# SEWERYN_G_ADYSZ_F1_DASHBOARD_SCHEMA_v3.net
KiCad netlist of a schematic drawn in EAGLE
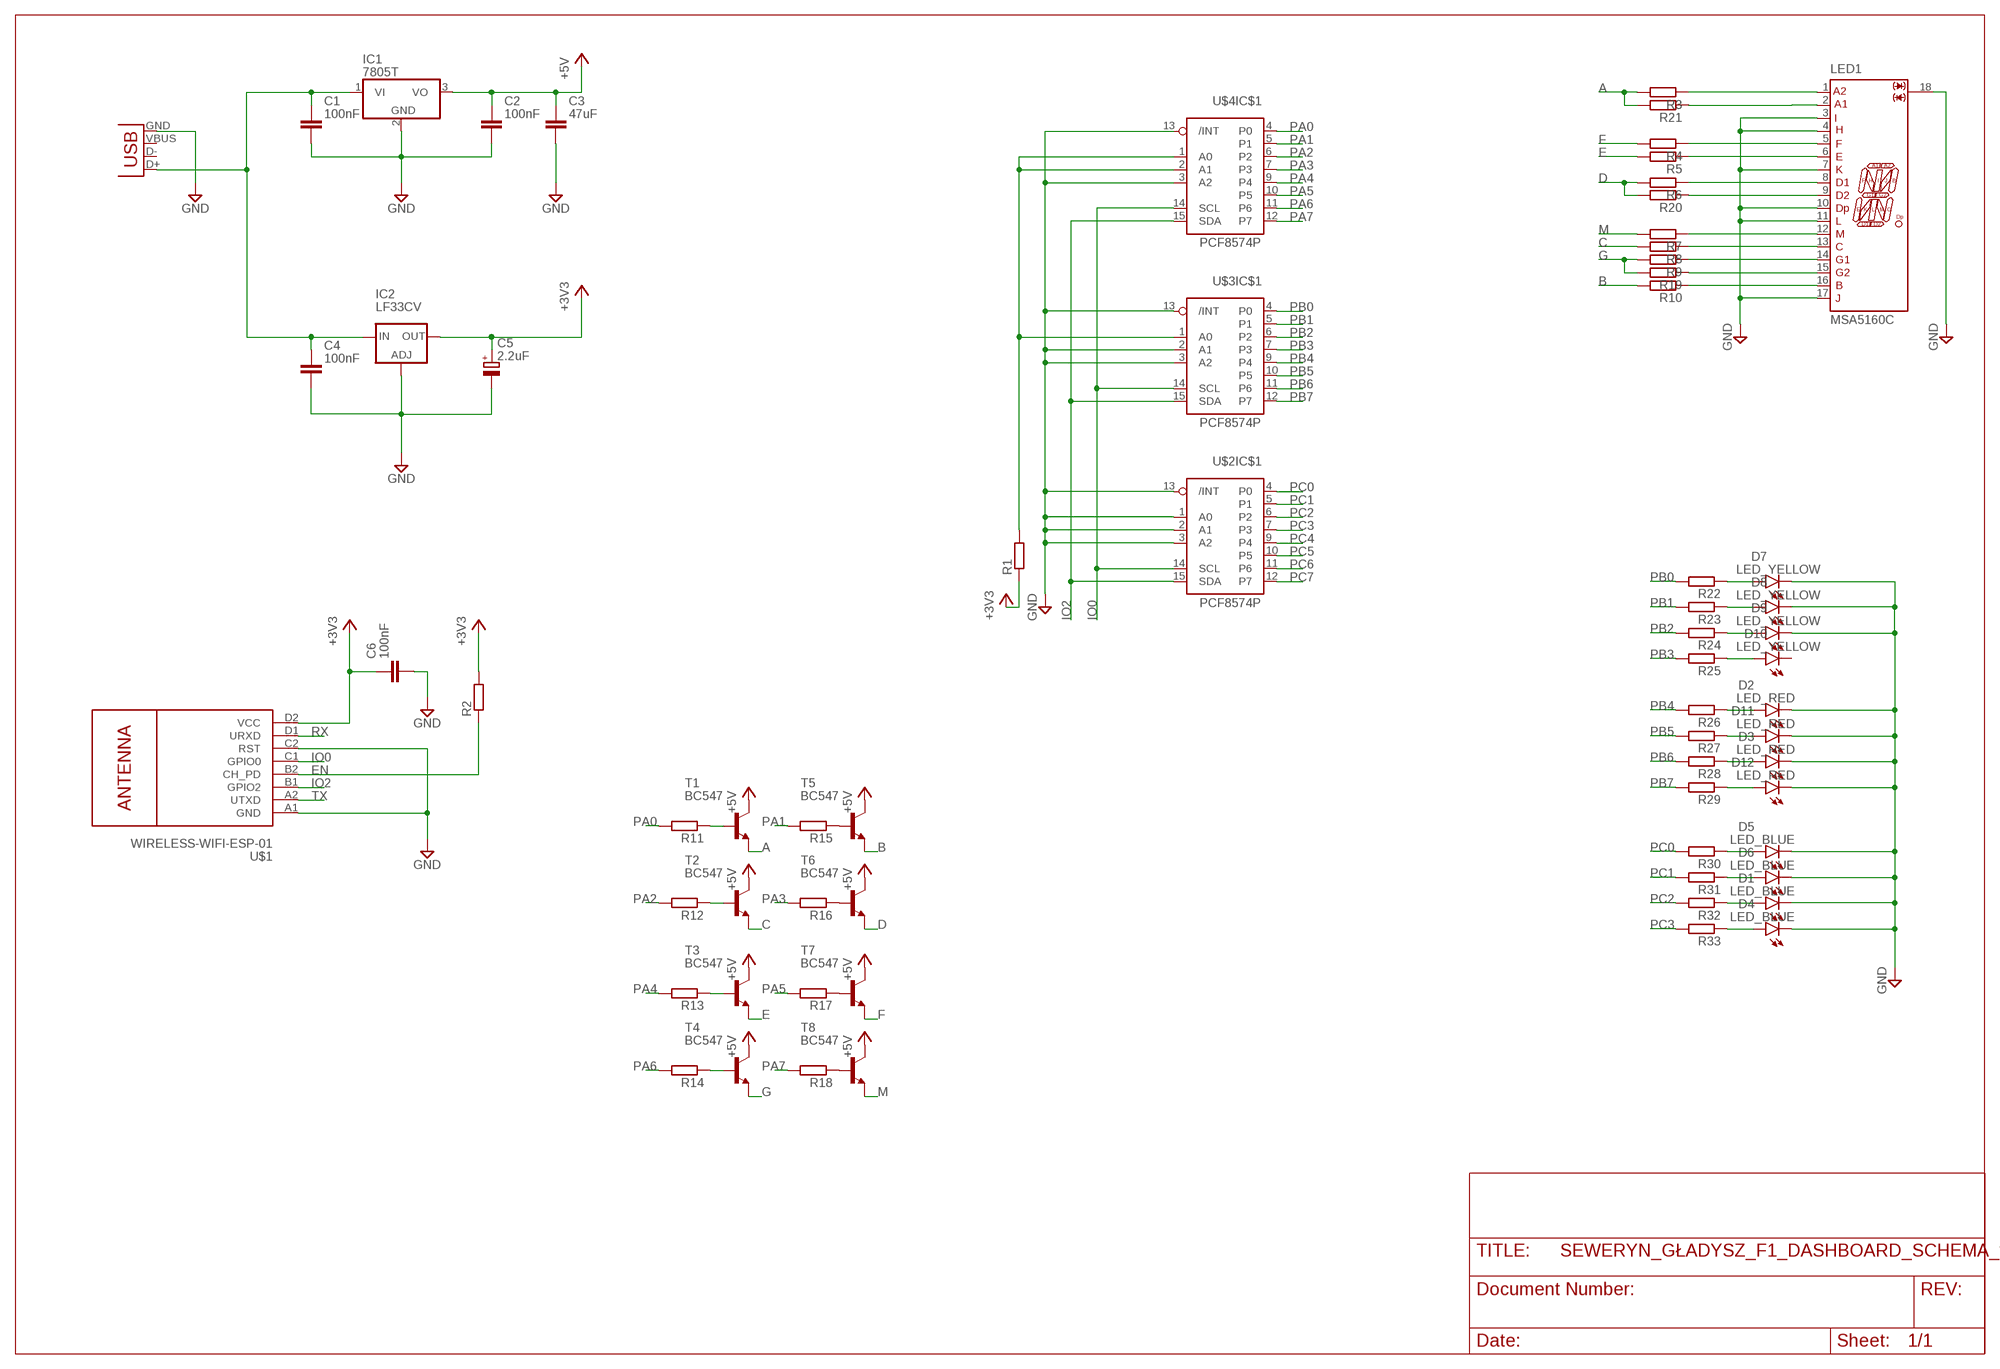
[diagram p0: schematic, sheet 1]

(export (version "E")
  (design (tool "Eeschema 10.0.6"))
  (components
    (comp (ref "C1")
      (value "100nF")
      (footprint "eagle-import:CAPRD550W60D1025H1250B")
      (libsource (lib "eagle-import") (part "CRADIAL-12.5MM-DIA_"))
    )
    (comp (ref "C2")
      (value "100nF")
      (footprint "eagle-import:CAPRD550W60D1025H1250B")
      (libsource (lib "eagle-import") (part "CRADIAL-12.5MM-DIA_"))
    )
    (comp (ref "C3")
      (value "47uF")
      (footprint "eagle-import:CAPRD550W60D1025H1250B")
      (libsource (lib "eagle-import") (part "CRADIAL-12.5MM-DIA_"))
    )
    (comp (ref "C4")
      (value "100nF")
      (footprint "eagle-import:CAPRD550W60D1025H1250B")
      (libsource (lib "eagle-import") (part "CRADIAL-12.5MM-DIA_"))
    )
    (comp (ref "C5")
      (value "2.2uF")
      (footprint "eagle-import:CAPPRD550W110D1250H2500B")
      (libsource (lib "eagle-import") (part "C-POLRADIAL-25MM-DIA_"))
    )
    (comp (ref "C6")
      (value "100nF")
      (footprint "eagle-import:CAPRD550W60D1025H1250B")
      (libsource (lib "eagle-import") (part "CRADIAL-12.5MM-DIA_"))
    )
    (comp (ref "D1")
      (value "LED_BLUE")
      (footprint "eagle-import:LEDRD254W60D565H860B_B")
      (libsource (lib "eagle-import") (part "LED_RADIALBLUE_"))
    )
    (comp (ref "D2")
      (value "LED_RED")
      (footprint "eagle-import:LEDRD254W60D565H860B")
      (libsource (lib "eagle-import") (part "LED_RADIALRED_"))
    )
    (comp (ref "D3")
      (value "LED_RED")
      (footprint "eagle-import:LEDRD254W60D565H860B")
      (libsource (lib "eagle-import") (part "LED_RADIALRED_"))
    )
    (comp (ref "D4")
      (value "LED_BLUE")
      (footprint "eagle-import:LEDRD254W60D565H860B_B")
      (libsource (lib "eagle-import") (part "LED_RADIALBLUE_"))
    )
    (comp (ref "D5")
      (value "LED_BLUE")
      (footprint "eagle-import:LEDRD254W60D565H860B_B")
      (libsource (lib "eagle-import") (part "LED_RADIALBLUE_"))
    )
    (comp (ref "D6")
      (value "LED_BLUE")
      (footprint "eagle-import:LEDRD254W60D565H860B_B")
      (libsource (lib "eagle-import") (part "LED_RADIALBLUE_"))
    )
    (comp (ref "D7")
      (value "LED_YELLOW")
      (footprint "eagle-import:LEDRD254W60D565H860B_Y")
      (libsource (lib "eagle-import") (part "LED_RADIALYELLOW_"))
    )
    (comp (ref "D8")
      (value "LED_YELLOW")
      (footprint "eagle-import:LEDRD254W60D565H860B_Y")
      (libsource (lib "eagle-import") (part "LED_RADIALYELLOW_"))
    )
    (comp (ref "D9")
      (value "LED_YELLOW")
      (footprint "eagle-import:LEDRD254W60D565H860B_Y")
      (libsource (lib "eagle-import") (part "LED_RADIALYELLOW_"))
    )
    (comp (ref "D10")
      (value "LED_YELLOW")
      (footprint "eagle-import:LEDRD254W60D565H860B_Y")
      (libsource (lib "eagle-import") (part "LED_RADIALYELLOW_"))
    )
    (comp (ref "D11")
      (value "LED_RED")
      (footprint "eagle-import:LEDRD254W60D565H860B")
      (libsource (lib "eagle-import") (part "LED_RADIALRED_"))
    )
    (comp (ref "D12")
      (value "LED_RED")
      (footprint "eagle-import:LEDRD254W60D565H860B")
      (libsource (lib "eagle-import") (part "LED_RADIALRED_"))
    )
    (comp (ref "IC1")
      (value "7805T")
      (footprint "eagle-import:TO220H")
      (libsource (lib "eagle-import") (part "78T05"))
    )
    (comp (ref "IC2")
      (value "LF33CV")
      (footprint "eagle-import:317TS")
      (libsource (lib "eagle-import") (part "LM317TS"))
    )
    (comp (ref "LED1")
      (value "MSA5160C")
      (footprint "eagle-import:MSA5XXX")
      (libsource (lib "eagle-import") (part "MSA5C160"))
    )
    (comp (ref "R1")
      (value "R-EU_0207/10")
      (footprint "eagle-import:0207_10")
      (libsource (lib "eagle-import") (part "R-EU_0207/10"))
    )
    (comp (ref "R2")
      (value "R-EU_0207/10")
      (footprint "eagle-import:0207_10")
      (libsource (lib "eagle-import") (part "R-EU_0207/10"))
    )
    (comp (ref "R3")
      (value "R-EU_0207/10")
      (footprint "eagle-import:0207_10")
      (libsource (lib "eagle-import") (part "R-EU_0207/10"))
    )
    (comp (ref "R4")
      (value "R-EU_0207/10")
      (footprint "eagle-import:0207_10")
      (libsource (lib "eagle-import") (part "R-EU_0207/10"))
    )
    (comp (ref "R5")
      (value "R-EU_0207/10")
      (footprint "eagle-import:0207_10")
      (libsource (lib "eagle-import") (part "R-EU_0207/10"))
    )
    (comp (ref "R6")
      (value "R-EU_0207/10")
      (footprint "eagle-import:0207_10")
      (libsource (lib "eagle-import") (part "R-EU_0207/10"))
    )
    (comp (ref "R7")
      (value "R-EU_0207/10")
      (footprint "eagle-import:0207_10")
      (libsource (lib "eagle-import") (part "R-EU_0207/10"))
    )
    (comp (ref "R8")
      (value "R-EU_0207/10")
      (footprint "eagle-import:0207_10")
      (libsource (lib "eagle-import") (part "R-EU_0207/10"))
    )
    (comp (ref "R9")
      (value "R-EU_0207/10")
      (footprint "eagle-import:0207_10")
      (libsource (lib "eagle-import") (part "R-EU_0207/10"))
    )
    (comp (ref "R10")
      (value "R-EU_0207/10")
      (footprint "eagle-import:0207_10")
      (libsource (lib "eagle-import") (part "R-EU_0207/10"))
    )
    (comp (ref "R11")
      (value "R-EU_0207/10")
      (footprint "eagle-import:0207_10")
      (libsource (lib "eagle-import") (part "R-EU_0207/10"))
    )
    (comp (ref "R12")
      (value "R-EU_0207/10")
      (footprint "eagle-import:0207_10")
      (libsource (lib "eagle-import") (part "R-EU_0207/10"))
    )
    (comp (ref "R13")
      (value "R-EU_0207/10")
      (footprint "eagle-import:0207_10")
      (libsource (lib "eagle-import") (part "R-EU_0207/10"))
    )
    (comp (ref "R14")
      (value "R-EU_0207/10")
      (footprint "eagle-import:0207_10")
      (libsource (lib "eagle-import") (part "R-EU_0207/10"))
    )
    (comp (ref "R15")
      (value "R-EU_0207/10")
      (footprint "eagle-import:0207_10")
      (libsource (lib "eagle-import") (part "R-EU_0207/10"))
    )
    (comp (ref "R16")
      (value "R-EU_0207/10")
      (footprint "eagle-import:0207_10")
      (libsource (lib "eagle-import") (part "R-EU_0207/10"))
    )
    (comp (ref "R17")
      (value "R-EU_0207/10")
      (footprint "eagle-import:0207_10")
      (libsource (lib "eagle-import") (part "R-EU_0207/10"))
    )
    (comp (ref "R18")
      (value "R-EU_0207/10")
      (footprint "eagle-import:0207_10")
      (libsource (lib "eagle-import") (part "R-EU_0207/10"))
    )
    (comp (ref "R19")
      (value "R-EU_0207/10")
      (footprint "eagle-import:0207_10")
      (libsource (lib "eagle-import") (part "R-EU_0207/10"))
    )
    (comp (ref "R20")
      (value "R-EU_0207/10")
      (footprint "eagle-import:0207_10")
      (libsource (lib "eagle-import") (part "R-EU_0207/10"))
    )
    (comp (ref "R21")
      (value "R-EU_0207/10")
      (footprint "eagle-import:0207_10")
      (libsource (lib "eagle-import") (part "R-EU_0207/10"))
    )
    (comp (ref "R22")
      (value "R-EU_0207/10")
      (footprint "eagle-import:0207_10")
      (libsource (lib "eagle-import") (part "R-EU_0207/10"))
    )
    (comp (ref "R23")
      (value "R-EU_0207/10")
      (footprint "eagle-import:0207_10")
      (libsource (lib "eagle-import") (part "R-EU_0207/10"))
    )
    (comp (ref "R24")
      (value "R-EU_0207/10")
      (footprint "eagle-import:0207_10")
      (libsource (lib "eagle-import") (part "R-EU_0207/10"))
    )
    (comp (ref "R25")
      (value "R-EU_0207/10")
      (footprint "eagle-import:0207_10")
      (libsource (lib "eagle-import") (part "R-EU_0207/10"))
    )
    (comp (ref "R26")
      (value "R-EU_0207/10")
      (footprint "eagle-import:0207_10")
      (libsource (lib "eagle-import") (part "R-EU_0207/10"))
    )
    (comp (ref "R27")
      (value "R-EU_0207/10")
      (footprint "eagle-import:0207_10")
      (libsource (lib "eagle-import") (part "R-EU_0207/10"))
    )
    (comp (ref "R28")
      (value "R-EU_0207/10")
      (footprint "eagle-import:0207_10")
      (libsource (lib "eagle-import") (part "R-EU_0207/10"))
    )
    (comp (ref "R29")
      (value "R-EU_0207/10")
      (footprint "eagle-import:0207_10")
      (libsource (lib "eagle-import") (part "R-EU_0207/10"))
    )
    (comp (ref "R30")
      (value "R-EU_0207/10")
      (footprint "eagle-import:0207_10")
      (libsource (lib "eagle-import") (part "R-EU_0207/10"))
    )
    (comp (ref "R31")
      (value "R-EU_0207/10")
      (footprint "eagle-import:0207_10")
      (libsource (lib "eagle-import") (part "R-EU_0207/10"))
    )
    (comp (ref "R32")
      (value "R-EU_0207/10")
      (footprint "eagle-import:0207_10")
      (libsource (lib "eagle-import") (part "R-EU_0207/10"))
    )
    (comp (ref "R33")
      (value "R-EU_0207/10")
      (footprint "eagle-import:0207_10")
      (libsource (lib "eagle-import") (part "R-EU_0207/10"))
    )
    (comp (ref "T1")
      (value "BC547")
      (footprint "eagle-import:TO92")
      (libsource (lib "eagle-import") (part "BC547"))
    )
    (comp (ref "T2")
      (value "BC547")
      (footprint "eagle-import:TO92")
      (libsource (lib "eagle-import") (part "BC547"))
    )
    (comp (ref "T3")
      (value "BC547")
      (footprint "eagle-import:TO92")
      (libsource (lib "eagle-import") (part "BC547"))
    )
    (comp (ref "T4")
      (value "BC547")
      (footprint "eagle-import:TO92")
      (libsource (lib "eagle-import") (part "BC547"))
    )
    (comp (ref "T5")
      (value "BC547")
      (footprint "eagle-import:TO92")
      (libsource (lib "eagle-import") (part "BC547"))
    )
    (comp (ref "T6")
      (value "BC547")
      (footprint "eagle-import:TO92")
      (libsource (lib "eagle-import") (part "BC547"))
    )
    (comp (ref "T7")
      (value "BC547")
      (footprint "eagle-import:TO92")
      (libsource (lib "eagle-import") (part "BC547"))
    )
    (comp (ref "T8")
      (value "BC547")
      (footprint "eagle-import:TO92")
      (libsource (lib "eagle-import") (part "BC547"))
    )
    (comp (ref "U$1")
      (value "WIRELESS-WIFI-ESP-01")
      (footprint "eagle-import:WIRELESS-WIFI-ESP-01")
      (libsource (lib "eagle-import") (part "WIRELESS-WIFI-ESP-01"))
    )
    (comp (ref "U$2")
      (value "PCF8574P")
      (footprint "eagle-import:DIL16")
      (libsource (lib "eagle-import") (part "PCF8574P"))
    )
    (comp (ref "U$3")
      (value "PCF8574P")
      (footprint "eagle-import:DIL16")
      (libsource (lib "eagle-import") (part "PCF8574P"))
    )
    (comp (ref "U$4")
      (value "PCF8574P")
      (footprint "eagle-import:DIL16")
      (libsource (lib "eagle-import") (part "PCF8574P"))
    )
    (comp (ref "X1")
      (value "USB-A-H")
      (footprint "eagle-import:USB-A-H")
      (libsource (lib "eagle-import") (part "USB-A-H"))
    )
  )
  (nets
    (net (code "1") (name "+3V3") (class "Default")
      (node (ref "C5") (pin "1") (pinfunction "+_1") (pintype "passive"))
      (node (ref "C6") (pin "1") (pinfunction "1_1") (pintype "passive"))
      (node (ref "IC2") (pin "2") (pinfunction "OUT_2") (pintype "passive"))
      (node (ref "R1") (pin "1") (pinfunction "1_1") (pintype "passive"))
      (node (ref "R2") (pin "2") (pinfunction "2_2") (pintype "passive"))
      (node (ref "U$1") (pin "D2") (pinfunction "VCC_D2") (pintype "power_in"))
    )
    (net (code "2") (name "+5V") (class "Default")
      (node (ref "C2") (pin "1") (pinfunction "1_1") (pintype "passive"))
      (node (ref "C3") (pin "1") (pinfunction "1_1") (pintype "passive"))
      (node (ref "IC1") (pin "3") (pinfunction "VO_3") (pintype "passive"))
      (node (ref "T1") (pin "3") (pinfunction "C_3") (pintype "passive"))
      (node (ref "T2") (pin "3") (pinfunction "C_3") (pintype "passive"))
      (node (ref "T3") (pin "3") (pinfunction "C_3") (pintype "passive"))
      (node (ref "T4") (pin "3") (pinfunction "C_3") (pintype "passive"))
      (node (ref "T5") (pin "3") (pinfunction "C_3") (pintype "passive"))
      (node (ref "T6") (pin "3") (pinfunction "C_3") (pintype "passive"))
      (node (ref "T7") (pin "3") (pinfunction "C_3") (pintype "passive"))
      (node (ref "T8") (pin "3") (pinfunction "C_3") (pintype "passive"))
    )
    (net (code "3") (name "/A") (class "Default")
      (node (ref "LED1") (pin "1") (pinfunction "1_1") (pintype "passive"))
      (node (ref "R21") (pin "2") (pinfunction "2_2") (pintype "passive"))
      (node (ref "R3") (pin "1") (pinfunction "1_1") (pintype "passive"))
      (node (ref "R3") (pin "2") (pinfunction "2_2") (pintype "passive"))
      (node (ref "T1") (pin "1") (pinfunction "E_1") (pintype "passive"))
    )
    (net (code "4") (name "/B") (class "Default")
      (node (ref "LED1") (pin "16") (pinfunction "16_16") (pintype "passive"))
      (node (ref "R10") (pin "1") (pinfunction "1_1") (pintype "passive"))
      (node (ref "R10") (pin "2") (pinfunction "2_2") (pintype "passive"))
      (node (ref "T5") (pin "1") (pinfunction "E_1") (pintype "passive"))
    )
    (net (code "5") (name "/C") (class "Default")
      (node (ref "LED1") (pin "13") (pinfunction "13_13") (pintype "passive"))
      (node (ref "R8") (pin "1") (pinfunction "1_1") (pintype "passive"))
      (node (ref "R8") (pin "2") (pinfunction "2_2") (pintype "passive"))
      (node (ref "T2") (pin "1") (pinfunction "E_1") (pintype "passive"))
    )
    (net (code "6") (name "/D") (class "Default")
      (node (ref "LED1") (pin "8") (pinfunction "8_8") (pintype "passive"))
      (node (ref "R20") (pin "2") (pinfunction "2_2") (pintype "passive"))
      (node (ref "R6") (pin "1") (pinfunction "1_1") (pintype "passive"))
      (node (ref "R6") (pin "2") (pinfunction "2_2") (pintype "passive"))
      (node (ref "T6") (pin "1") (pinfunction "E_1") (pintype "passive"))
    )
    (net (code "7") (name "/E") (class "Default")
      (node (ref "LED1") (pin "6") (pinfunction "6_6") (pintype "passive"))
      (node (ref "R5") (pin "1") (pinfunction "1_1") (pintype "passive"))
      (node (ref "R5") (pin "2") (pinfunction "2_2") (pintype "passive"))
      (node (ref "T3") (pin "1") (pinfunction "E_1") (pintype "passive"))
    )
    (net (code "8") (name "/EN") (class "Default")
      (node (ref "R2") (pin "1") (pinfunction "1_1") (pintype "passive"))
      (node (ref "U$1") (pin "B2") (pinfunction "CH_PD_B2") (pintype "bidirectional"))
    )
    (net (code "9") (name "/F") (class "Default")
      (node (ref "LED1") (pin "5") (pinfunction "5_5") (pintype "passive"))
      (node (ref "R4") (pin "1") (pinfunction "1_1") (pintype "passive"))
      (node (ref "R4") (pin "2") (pinfunction "2_2") (pintype "passive"))
      (node (ref "T7") (pin "1") (pinfunction "E_1") (pintype "passive"))
    )
    (net (code "10") (name "/G") (class "Default")
      (node (ref "LED1") (pin "14") (pinfunction "14_14") (pintype "passive"))
      (node (ref "R19") (pin "2") (pinfunction "2_2") (pintype "passive"))
      (node (ref "R9") (pin "1") (pinfunction "1_1") (pintype "passive"))
      (node (ref "R9") (pin "2") (pinfunction "2_2") (pintype "passive"))
      (node (ref "T4") (pin "1") (pinfunction "E_1") (pintype "passive"))
    )
    (net (code "11") (name "/IO0") (class "Default")
      (node (ref "U$1") (pin "C1") (pinfunction "GPIO0_C1") (pintype "bidirectional"))
      (node (ref "U$2") (pin "14") (pinfunction "SCL_14") (pintype "input"))
      (node (ref "U$3") (pin "14") (pinfunction "SCL_14") (pintype "input"))
      (node (ref "U$4") (pin "14") (pinfunction "SCL_14") (pintype "input"))
    )
    (net (code "12") (name "/IO2") (class "Default")
      (node (ref "U$1") (pin "B1") (pinfunction "GPIO2_B1") (pintype "bidirectional"))
      (node (ref "U$2") (pin "15") (pinfunction "SDA_15") (pintype "bidirectional"))
      (node (ref "U$3") (pin "15") (pinfunction "SDA_15") (pintype "bidirectional"))
      (node (ref "U$4") (pin "15") (pinfunction "SDA_15") (pintype "bidirectional"))
    )
    (net (code "13") (name "/M") (class "Default")
      (node (ref "LED1") (pin "12") (pinfunction "12_12") (pintype "passive"))
      (node (ref "R7") (pin "1") (pinfunction "1_1") (pintype "passive"))
      (node (ref "R7") (pin "2") (pinfunction "2_2") (pintype "passive"))
      (node (ref "T8") (pin "1") (pinfunction "E_1") (pintype "passive"))
    )
    (net (code "14") (name "/PA0") (class "Default")
      (node (ref "R11") (pin "2") (pinfunction "2_2") (pintype "passive"))
      (node (ref "U$4") (pin "4") (pinfunction "P0_4") (pintype "bidirectional"))
    )
    (net (code "15") (name "/PA1") (class "Default")
      (node (ref "R15") (pin "2") (pinfunction "2_2") (pintype "passive"))
      (node (ref "U$4") (pin "5") (pinfunction "P1_5") (pintype "bidirectional"))
    )
    (net (code "16") (name "/PA2") (class "Default")
      (node (ref "R12") (pin "2") (pinfunction "2_2") (pintype "passive"))
      (node (ref "U$4") (pin "6") (pinfunction "P2_6") (pintype "bidirectional"))
    )
    (net (code "17") (name "/PA3") (class "Default")
      (node (ref "R16") (pin "2") (pinfunction "2_2") (pintype "passive"))
      (node (ref "U$4") (pin "7") (pinfunction "P3_7") (pintype "bidirectional"))
    )
    (net (code "18") (name "/PA4") (class "Default")
      (node (ref "R13") (pin "2") (pinfunction "2_2") (pintype "passive"))
      (node (ref "U$4") (pin "9") (pinfunction "P4_9") (pintype "bidirectional"))
    )
    (net (code "19") (name "/PA5") (class "Default")
      (node (ref "R17") (pin "2") (pinfunction "2_2") (pintype "passive"))
      (node (ref "U$4") (pin "10") (pinfunction "P5_10") (pintype "bidirectional"))
    )
    (net (code "20") (name "/PA6") (class "Default")
      (node (ref "R14") (pin "2") (pinfunction "2_2") (pintype "passive"))
      (node (ref "U$4") (pin "11") (pinfunction "P6_11") (pintype "bidirectional"))
    )
    (net (code "21") (name "/PA7") (class "Default")
      (node (ref "R18") (pin "2") (pinfunction "2_2") (pintype "passive"))
      (node (ref "U$4") (pin "12") (pinfunction "P7_12") (pintype "bidirectional"))
    )
    (net (code "22") (name "/PB0") (class "Default")
      (node (ref "R22") (pin "2") (pinfunction "2_2") (pintype "passive"))
      (node (ref "U$3") (pin "4") (pinfunction "P0_4") (pintype "bidirectional"))
    )
    (net (code "23") (name "/PB1") (class "Default")
      (node (ref "R23") (pin "2") (pinfunction "2_2") (pintype "passive"))
      (node (ref "U$3") (pin "5") (pinfunction "P1_5") (pintype "bidirectional"))
    )
    (net (code "24") (name "/PB2") (class "Default")
      (node (ref "R24") (pin "2") (pinfunction "2_2") (pintype "passive"))
      (node (ref "U$3") (pin "6") (pinfunction "P2_6") (pintype "bidirectional"))
    )
    (net (code "25") (name "/PB3") (class "Default")
      (node (ref "R25") (pin "2") (pinfunction "2_2") (pintype "passive"))
      (node (ref "U$3") (pin "7") (pinfunction "P3_7") (pintype "bidirectional"))
    )
    (net (code "26") (name "/PB4") (class "Default")
      (node (ref "R26") (pin "2") (pinfunction "2_2") (pintype "passive"))
      (node (ref "U$3") (pin "9") (pinfunction "P4_9") (pintype "bidirectional"))
    )
    (net (code "27") (name "/PB5") (class "Default")
      (node (ref "R27") (pin "2") (pinfunction "2_2") (pintype "passive"))
      (node (ref "U$3") (pin "10") (pinfunction "P5_10") (pintype "bidirectional"))
    )
    (net (code "28") (name "/PB6") (class "Default")
      (node (ref "R28") (pin "2") (pinfunction "2_2") (pintype "passive"))
      (node (ref "U$3") (pin "11") (pinfunction "P6_11") (pintype "bidirectional"))
    )
    (net (code "29") (name "/PB7") (class "Default")
      (node (ref "R29") (pin "2") (pinfunction "2_2") (pintype "passive"))
      (node (ref "U$3") (pin "12") (pinfunction "P7_12") (pintype "bidirectional"))
    )
    (net (code "30") (name "/PC0") (class "Default")
      (node (ref "R30") (pin "2") (pinfunction "2_2") (pintype "passive"))
      (node (ref "U$2") (pin "4") (pinfunction "P0_4") (pintype "bidirectional"))
    )
    (net (code "31") (name "/PC1") (class "Default")
      (node (ref "R31") (pin "2") (pinfunction "2_2") (pintype "passive"))
      (node (ref "U$2") (pin "5") (pinfunction "P1_5") (pintype "bidirectional"))
    )
    (net (code "32") (name "/PC2") (class "Default")
      (node (ref "R32") (pin "2") (pinfunction "2_2") (pintype "passive"))
      (node (ref "U$2") (pin "6") (pinfunction "P2_6") (pintype "bidirectional"))
    )
    (net (code "33") (name "/PC3") (class "Default")
      (node (ref "R33") (pin "2") (pinfunction "2_2") (pintype "passive"))
      (node (ref "U$2") (pin "7") (pinfunction "P3_7") (pintype "bidirectional"))
    )
    (net (code "34") (name "/PC4") (class "Default")
      (node (ref "U$2") (pin "9") (pinfunction "P4_9") (pintype "bidirectional"))
    )
    (net (code "35") (name "/PC5") (class "Default")
      (node (ref "U$2") (pin "10") (pinfunction "P5_10") (pintype "bidirectional"))
    )
    (net (code "36") (name "/PC6") (class "Default")
      (node (ref "U$2") (pin "11") (pinfunction "P6_11") (pintype "bidirectional"))
    )
    (net (code "37") (name "/PC7") (class "Default")
      (node (ref "U$2") (pin "12") (pinfunction "P7_12") (pintype "bidirectional"))
    )
    (net (code "38") (name "/RX") (class "Default")
      (node (ref "U$1") (pin "D1") (pinfunction "URXD_D1") (pintype "bidirectional"))
    )
    (net (code "39") (name "/TX") (class "Default")
      (node (ref "U$1") (pin "A2") (pinfunction "UTXD_A2") (pintype "bidirectional"))
    )
    (net (code "40") (name "GND") (class "Default")
      (node (ref "C1") (pin "2") (pinfunction "2_2") (pintype "passive"))
      (node (ref "C2") (pin "2") (pinfunction "2_2") (pintype "passive"))
      (node (ref "C3") (pin "2") (pinfunction "2_2") (pintype "passive"))
      (node (ref "C4") (pin "2") (pinfunction "2_2") (pintype "passive"))
      (node (ref "C5") (pin "2") (pinfunction "-_2") (pintype "passive"))
      (node (ref "C6") (pin "2") (pinfunction "2_2") (pintype "passive"))
      (node (ref "D1") (pin "2") (pinfunction "C_2") (pintype "passive"))
      (node (ref "D11") (pin "2") (pinfunction "C_2") (pintype "passive"))
      (node (ref "D12") (pin "2") (pinfunction "C_2") (pintype "passive"))
      (node (ref "D2") (pin "2") (pinfunction "C_2") (pintype "passive"))
      (node (ref "D3") (pin "2") (pinfunction "C_2") (pintype "passive"))
      (node (ref "D4") (pin "2") (pinfunction "C_2") (pintype "passive"))
      (node (ref "D5") (pin "2") (pinfunction "C_2") (pintype "passive"))
      (node (ref "D6") (pin "2") (pinfunction "C_2") (pintype "passive"))
      (node (ref "D7") (pin "2") (pinfunction "C_2") (pintype "passive"))
      (node (ref "D8") (pin "2") (pinfunction "C_2") (pintype "passive"))
      (node (ref "D9") (pin "2") (pinfunction "C_2") (pintype "passive"))
      (node (ref "IC1") (pin "2") (pinfunction "GND_2") (pintype "passive"))
      (node (ref "IC2") (pin "1") (pinfunction "ADJ_1") (pintype "input"))
      (node (ref "LED1") (pin "10") (pinfunction "10_10") (pintype "passive"))
      (node (ref "LED1") (pin "11") (pinfunction "11_11") (pintype "passive"))
      (node (ref "LED1") (pin "17") (pinfunction "17_17") (pintype "passive"))
      (node (ref "LED1") (pin "18") (pinfunction "18_18") (pintype "passive"))
      (node (ref "LED1") (pin "3") (pinfunction "3_3") (pintype "passive"))
      (node (ref "LED1") (pin "4") (pinfunction "4_4") (pintype "passive"))
      (node (ref "LED1") (pin "7") (pinfunction "7_7") (pintype "passive"))
      (node (ref "U$1") (pin "A1") (pinfunction "GND_A1") (pintype "power_in"))
      (node (ref "U$1") (pin "C2") (pinfunction "RST_C2") (pintype "bidirectional"))
      (node (ref "U$2") (pin "1") (pinfunction "A0_1") (pintype "input"))
      (node (ref "U$2") (pin "13") (pinfunction "/INT_13") (pintype "output"))
      (node (ref "U$2") (pin "2") (pinfunction "A1_2") (pintype "input"))
      (node (ref "U$2") (pin "3") (pinfunction "A2_3") (pintype "input"))
      (node (ref "U$3") (pin "13") (pinfunction "/INT_13") (pintype "output"))
      (node (ref "U$3") (pin "2") (pinfunction "A1_2") (pintype "input"))
      (node (ref "U$3") (pin "3") (pinfunction "A2_3") (pintype "input"))
      (node (ref "U$4") (pin "13") (pinfunction "/INT_13") (pintype "output"))
      (node (ref "U$4") (pin "3") (pinfunction "A2_3") (pintype "input"))
      (node (ref "X1") (pin "GND") (pinfunction "GND_GND") (pintype "bidirectional"))
    )
    (net (code "41") (name "Net-(D1-A)") (class "Default")
      (node (ref "D1") (pin "1") (pinfunction "A_1") (pintype "passive"))
      (node (ref "R32") (pin "1") (pinfunction "1_1") (pintype "passive"))
    )
    (net (code "42") (name "Net-(D2-A)") (class "Default")
      (node (ref "D2") (pin "1") (pinfunction "A_1") (pintype "passive"))
      (node (ref "R26") (pin "1") (pinfunction "1_1") (pintype "passive"))
    )
    (net (code "43") (name "Net-(D3-A)") (class "Default")
      (node (ref "D3") (pin "1") (pinfunction "A_1") (pintype "passive"))
      (node (ref "R28") (pin "1") (pinfunction "1_1") (pintype "passive"))
    )
    (net (code "44") (name "Net-(D4-A)") (class "Default")
      (node (ref "D4") (pin "1") (pinfunction "A_1") (pintype "passive"))
      (node (ref "R33") (pin "1") (pinfunction "1_1") (pintype "passive"))
    )
    (net (code "45") (name "Net-(D5-A)") (class "Default")
      (node (ref "D5") (pin "1") (pinfunction "A_1") (pintype "passive"))
      (node (ref "R30") (pin "1") (pinfunction "1_1") (pintype "passive"))
    )
    (net (code "46") (name "Net-(D6-A)") (class "Default")
      (node (ref "D6") (pin "1") (pinfunction "A_1") (pintype "passive"))
      (node (ref "R31") (pin "1") (pinfunction "1_1") (pintype "passive"))
    )
    (net (code "47") (name "Net-(D7-A)") (class "Default")
      (node (ref "D7") (pin "1") (pinfunction "A_1") (pintype "passive"))
      (node (ref "R22") (pin "1") (pinfunction "1_1") (pintype "passive"))
    )
    (net (code "48") (name "Net-(D8-A)") (class "Default")
      (node (ref "D8") (pin "1") (pinfunction "A_1") (pintype "passive"))
      (node (ref "R23") (pin "1") (pinfunction "1_1") (pintype "passive"))
    )
    (net (code "49") (name "Net-(D9-A)") (class "Default")
      (node (ref "D9") (pin "1") (pinfunction "A_1") (pintype "passive"))
      (node (ref "R24") (pin "1") (pinfunction "1_1") (pintype "passive"))
    )
    (net (code "50") (name "Net-(D10-A)") (class "Default")
      (node (ref "D10") (pin "1") (pinfunction "A_1") (pintype "passive"))
      (node (ref "R25") (pin "1") (pinfunction "1_1") (pintype "passive"))
    )
    (net (code "51") (name "Net-(D11-A)") (class "Default")
      (node (ref "D11") (pin "1") (pinfunction "A_1") (pintype "passive"))
      (node (ref "R27") (pin "1") (pinfunction "1_1") (pintype "passive"))
    )
    (net (code "52") (name "Net-(D12-A)") (class "Default")
      (node (ref "D12") (pin "1") (pinfunction "A_1") (pintype "passive"))
      (node (ref "R29") (pin "1") (pinfunction "1_1") (pintype "passive"))
    )
    (net (code "53") (name "Net-(IC1-VI)") (class "Default")
      (node (ref "C1") (pin "1") (pinfunction "1_1") (pintype "passive"))
      (node (ref "C4") (pin "1") (pinfunction "1_1") (pintype "passive"))
      (node (ref "IC1") (pin "1") (pinfunction "VI_1") (pintype "input"))
      (node (ref "IC2") (pin "3") (pinfunction "IN_3") (pintype "input"))
      (node (ref "X1") (pin "D+") (pinfunction "D+_D+") (pintype "bidirectional"))
    )
    (net (code "54") (name "Net-(LED1-Pad2)") (class "Default")
      (node (ref "LED1") (pin "2") (pinfunction "2_2") (pintype "passive"))
      (node (ref "R21") (pin "1") (pinfunction "1_1") (pintype "passive"))
    )
    (net (code "55") (name "Net-(LED1-Pad9)") (class "Default")
      (node (ref "LED1") (pin "9") (pinfunction "9_9") (pintype "passive"))
      (node (ref "R20") (pin "1") (pinfunction "1_1") (pintype "passive"))
    )
    (net (code "56") (name "Net-(LED1-Pad15)") (class "Default")
      (node (ref "LED1") (pin "15") (pinfunction "15_15") (pintype "passive"))
      (node (ref "R19") (pin "1") (pinfunction "1_1") (pintype "passive"))
    )
    (net (code "57") (name "Net-(T1-B)") (class "Default")
      (node (ref "R11") (pin "1") (pinfunction "1_1") (pintype "passive"))
      (node (ref "T1") (pin "2") (pinfunction "B_2") (pintype "passive"))
    )
    (net (code "58") (name "Net-(T2-B)") (class "Default")
      (node (ref "R12") (pin "1") (pinfunction "1_1") (pintype "passive"))
      (node (ref "T2") (pin "2") (pinfunction "B_2") (pintype "passive"))
    )
    (net (code "59") (name "Net-(T3-B)") (class "Default")
      (node (ref "R13") (pin "1") (pinfunction "1_1") (pintype "passive"))
      (node (ref "T3") (pin "2") (pinfunction "B_2") (pintype "passive"))
    )
    (net (code "60") (name "Net-(T4-B)") (class "Default")
      (node (ref "R14") (pin "1") (pinfunction "1_1") (pintype "passive"))
      (node (ref "T4") (pin "2") (pinfunction "B_2") (pintype "passive"))
    )
    (net (code "61") (name "Net-(T5-B)") (class "Default")
      (node (ref "R15") (pin "1") (pinfunction "1_1") (pintype "passive"))
      (node (ref "T5") (pin "2") (pinfunction "B_2") (pintype "passive"))
    )
    (net (code "62") (name "Net-(T6-B)") (class "Default")
      (node (ref "R16") (pin "1") (pinfunction "1_1") (pintype "passive"))
      (node (ref "T6") (pin "2") (pinfunction "B_2") (pintype "passive"))
    )
    (net (code "63") (name "Net-(T7-B)") (class "Default")
      (node (ref "R17") (pin "1") (pinfunction "1_1") (pintype "passive"))
      (node (ref "T7") (pin "2") (pinfunction "B_2") (pintype "passive"))
    )
    (net (code "64") (name "Net-(T8-B)") (class "Default")
      (node (ref "R18") (pin "1") (pinfunction "1_1") (pintype "passive"))
      (node (ref "T8") (pin "2") (pinfunction "B_2") (pintype "passive"))
    )
    (net (code "65") (name "Net-(U$3A-A0)") (class "Default")
      (node (ref "R1") (pin "2") (pinfunction "2_2") (pintype "passive"))
      (node (ref "U$3") (pin "1") (pinfunction "A0_1") (pintype "input"))
      (node (ref "U$4") (pin "1") (pinfunction "A0_1") (pintype "input"))
      (node (ref "U$4") (pin "2") (pinfunction "A1_2") (pintype "input"))
    )
    (net (code "66") (name "unconnected-(D10-C-Pad2)") (class "Default")
      (node (ref "D10") (pin "2") (pinfunction "C_2") (pintype "passive"))
    )
    (net (code "67") (name "unconnected-(X1-PadD-)") (class "Default")
      (node (ref "X1") (pin "D-") (pinfunction "D-_D-") (pintype "bidirectional"))
    )
    (net (code "68") (name "unconnected-(X1-PadVBUS)") (class "Default")
      (node (ref "X1") (pin "VBUS") (pinfunction "VBUS_VBUS") (pintype "bidirectional"))
    )
  )
)
